# SCH_SEGEMENTOS_HORA_2.net
KiCad netlist of a schematic drawn in Altium Designer
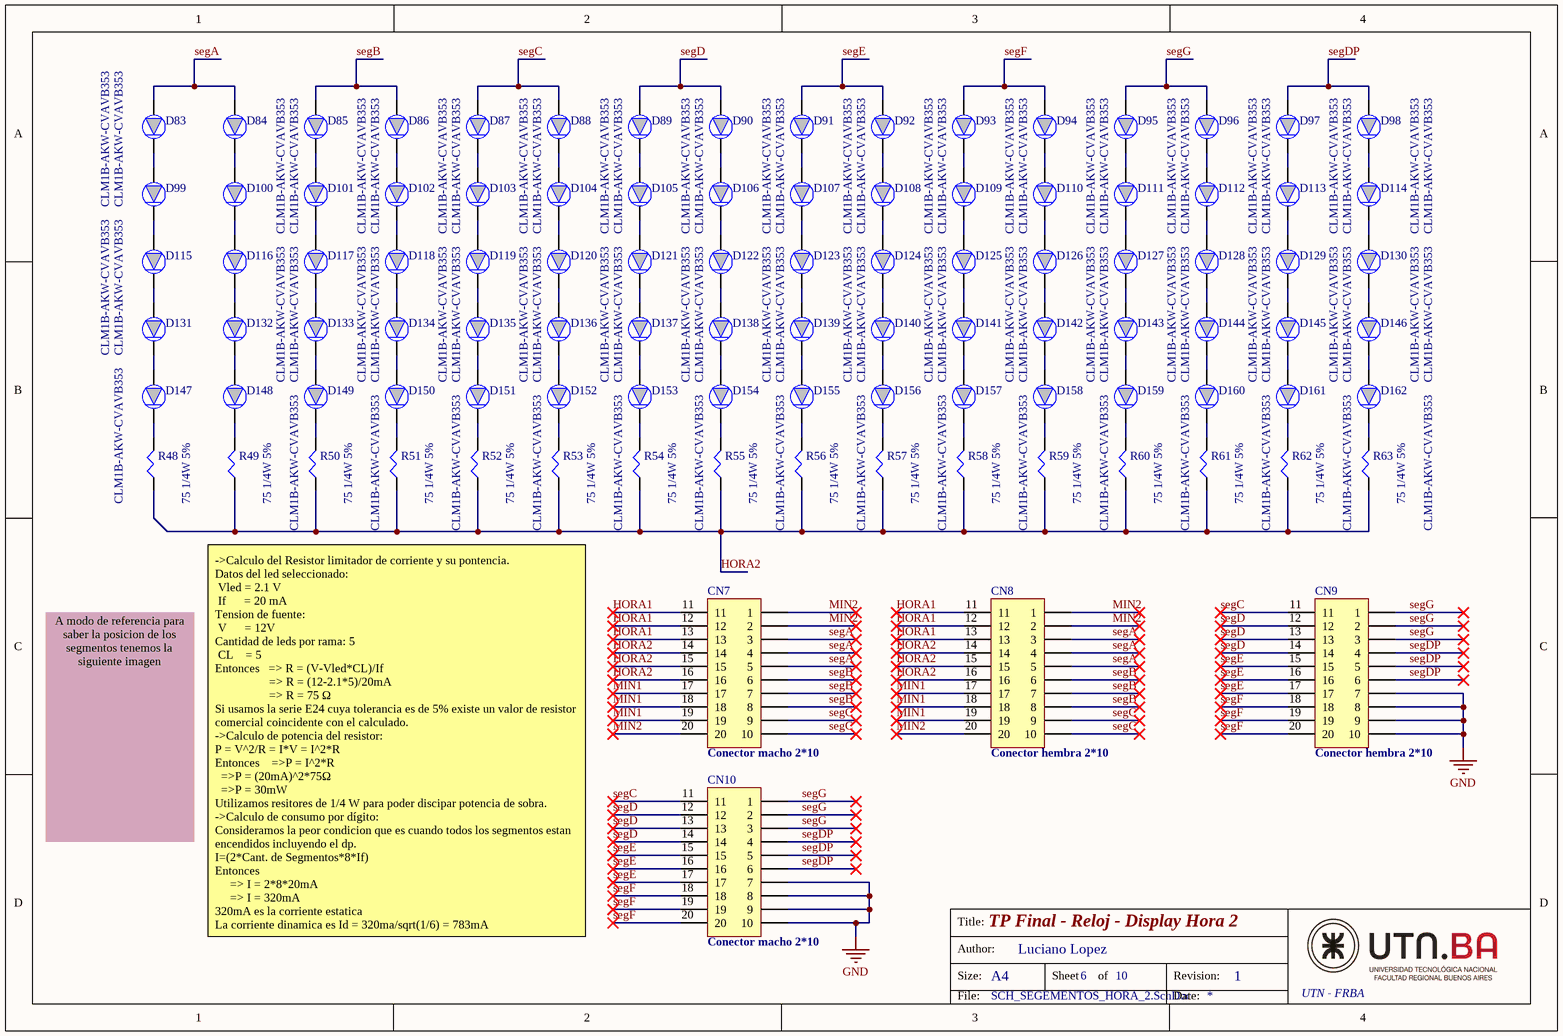
[diagram p0: SCH_SEGEMENTOS_HORA_2.SchDoc]

(export (version "E")
  (design (tool "Eeschema 10.0.6"))
  (components
    (comp (ref "CN7")
      (value "Conector macho 2*10")
      (description "Connector Generic 10 Vias")
      (libsource (lib "SCH_LIB") (part "CONN_2x10P"))
    )
    (comp (ref "CN8")
      (value "Conector hembra 2*10")
      (description "Connector Generic 10 Vias")
      (libsource (lib "SCH_LIB") (part "CONN_2x10P"))
    )
    (comp (ref "CN9")
      (value "Conector hembra 2*10")
      (description "Connector Generic 10 Vias")
      (libsource (lib "SCH_LIB") (part "CONN_2x10P"))
    )
    (comp (ref "CN10")
      (value "Conector macho 2*10")
      (description "Connector Generic 10 Vias")
      (libsource (lib "SCH_LIB") (part "CONN_2x10P"))
    )
    (comp (ref "D83")
      (value "CLM1B-AKW-CVAVB353")
      (footprint "PLCC2_LED")
      (libsource (lib "SCH_LIB") (part "LED_DIODE"))
    )
    (comp (ref "D84")
      (value "CLM1B-AKW-CVAVB353")
      (footprint "PLCC2_LED")
      (libsource (lib "SCH_LIB") (part "LED_DIODE"))
    )
    (comp (ref "D85")
      (value "CLM1B-AKW-CVAVB353")
      (footprint "PLCC2_LED")
      (libsource (lib "SCH_LIB") (part "LED_DIODE"))
    )
    (comp (ref "D86")
      (value "CLM1B-AKW-CVAVB353")
      (footprint "PLCC2_LED")
      (libsource (lib "SCH_LIB") (part "LED_DIODE"))
    )
    (comp (ref "D87")
      (value "CLM1B-AKW-CVAVB353")
      (footprint "PLCC2_LED")
      (libsource (lib "SCH_LIB") (part "LED_DIODE"))
    )
    (comp (ref "D88")
      (value "CLM1B-AKW-CVAVB353")
      (footprint "PLCC2_LED")
      (libsource (lib "SCH_LIB") (part "LED_DIODE"))
    )
    (comp (ref "D89")
      (value "CLM1B-AKW-CVAVB353")
      (footprint "PLCC2_LED")
      (libsource (lib "SCH_LIB") (part "LED_DIODE"))
    )
    (comp (ref "D90")
      (value "CLM1B-AKW-CVAVB353")
      (footprint "PLCC2_LED")
      (libsource (lib "SCH_LIB") (part "LED_DIODE"))
    )
    (comp (ref "D91")
      (value "CLM1B-AKW-CVAVB353")
      (footprint "PLCC2_LED")
      (libsource (lib "SCH_LIB") (part "LED_DIODE"))
    )
    (comp (ref "D92")
      (value "CLM1B-AKW-CVAVB353")
      (footprint "PLCC2_LED")
      (libsource (lib "SCH_LIB") (part "LED_DIODE"))
    )
    (comp (ref "D93")
      (value "CLM1B-AKW-CVAVB353")
      (footprint "PLCC2_LED")
      (libsource (lib "SCH_LIB") (part "LED_DIODE"))
    )
    (comp (ref "D94")
      (value "CLM1B-AKW-CVAVB353")
      (footprint "PLCC2_LED")
      (libsource (lib "SCH_LIB") (part "LED_DIODE"))
    )
    (comp (ref "D95")
      (value "CLM1B-AKW-CVAVB353")
      (footprint "PLCC2_LED")
      (libsource (lib "SCH_LIB") (part "LED_DIODE"))
    )
    (comp (ref "D96")
      (value "CLM1B-AKW-CVAVB353")
      (footprint "PLCC2_LED")
      (libsource (lib "SCH_LIB") (part "LED_DIODE"))
    )
    (comp (ref "D97")
      (value "CLM1B-AKW-CVAVB353")
      (footprint "PLCC2_LED")
      (libsource (lib "SCH_LIB") (part "LED_DIODE"))
    )
    (comp (ref "D98")
      (value "CLM1B-AKW-CVAVB353")
      (footprint "PLCC2_LED")
      (libsource (lib "SCH_LIB") (part "LED_DIODE"))
    )
    (comp (ref "D99")
      (value "CLM1B-AKW-CVAVB353")
      (footprint "PLCC2_LED")
      (libsource (lib "SCH_LIB") (part "LED_DIODE"))
    )
    (comp (ref "D100")
      (value "CLM1B-AKW-CVAVB353")
      (footprint "PLCC2_LED")
      (libsource (lib "SCH_LIB") (part "LED_DIODE"))
    )
    (comp (ref "D101")
      (value "CLM1B-AKW-CVAVB353")
      (footprint "PLCC2_LED")
      (libsource (lib "SCH_LIB") (part "LED_DIODE"))
    )
    (comp (ref "D102")
      (value "CLM1B-AKW-CVAVB353")
      (footprint "PLCC2_LED")
      (libsource (lib "SCH_LIB") (part "LED_DIODE"))
    )
    (comp (ref "D103")
      (value "CLM1B-AKW-CVAVB353")
      (footprint "PLCC2_LED")
      (libsource (lib "SCH_LIB") (part "LED_DIODE"))
    )
    (comp (ref "D104")
      (value "CLM1B-AKW-CVAVB353")
      (footprint "PLCC2_LED")
      (libsource (lib "SCH_LIB") (part "LED_DIODE"))
    )
    (comp (ref "D105")
      (value "CLM1B-AKW-CVAVB353")
      (footprint "PLCC2_LED")
      (libsource (lib "SCH_LIB") (part "LED_DIODE"))
    )
    (comp (ref "D106")
      (value "CLM1B-AKW-CVAVB353")
      (footprint "PLCC2_LED")
      (libsource (lib "SCH_LIB") (part "LED_DIODE"))
    )
    (comp (ref "D107")
      (value "CLM1B-AKW-CVAVB353")
      (footprint "PLCC2_LED")
      (libsource (lib "SCH_LIB") (part "LED_DIODE"))
    )
    (comp (ref "D108")
      (value "CLM1B-AKW-CVAVB353")
      (footprint "PLCC2_LED")
      (libsource (lib "SCH_LIB") (part "LED_DIODE"))
    )
    (comp (ref "D109")
      (value "CLM1B-AKW-CVAVB353")
      (footprint "PLCC2_LED")
      (libsource (lib "SCH_LIB") (part "LED_DIODE"))
    )
    (comp (ref "D110")
      (value "CLM1B-AKW-CVAVB353")
      (footprint "PLCC2_LED")
      (libsource (lib "SCH_LIB") (part "LED_DIODE"))
    )
    (comp (ref "D111")
      (value "CLM1B-AKW-CVAVB353")
      (footprint "PLCC2_LED")
      (libsource (lib "SCH_LIB") (part "LED_DIODE"))
    )
    (comp (ref "D112")
      (value "CLM1B-AKW-CVAVB353")
      (footprint "PLCC2_LED")
      (libsource (lib "SCH_LIB") (part "LED_DIODE"))
    )
    (comp (ref "D113")
      (value "CLM1B-AKW-CVAVB353")
      (footprint "PLCC2_LED")
      (libsource (lib "SCH_LIB") (part "LED_DIODE"))
    )
    (comp (ref "D114")
      (value "CLM1B-AKW-CVAVB353")
      (footprint "PLCC2_LED")
      (libsource (lib "SCH_LIB") (part "LED_DIODE"))
    )
    (comp (ref "D115")
      (value "CLM1B-AKW-CVAVB353")
      (footprint "PLCC2_LED")
      (libsource (lib "SCH_LIB") (part "LED_DIODE"))
    )
    (comp (ref "D116")
      (value "CLM1B-AKW-CVAVB353")
      (footprint "PLCC2_LED")
      (libsource (lib "SCH_LIB") (part "LED_DIODE"))
    )
    (comp (ref "D117")
      (value "CLM1B-AKW-CVAVB353")
      (footprint "PLCC2_LED")
      (libsource (lib "SCH_LIB") (part "LED_DIODE"))
    )
    (comp (ref "D118")
      (value "CLM1B-AKW-CVAVB353")
      (footprint "PLCC2_LED")
      (libsource (lib "SCH_LIB") (part "LED_DIODE"))
    )
    (comp (ref "D119")
      (value "CLM1B-AKW-CVAVB353")
      (footprint "PLCC2_LED")
      (libsource (lib "SCH_LIB") (part "LED_DIODE"))
    )
    (comp (ref "D120")
      (value "CLM1B-AKW-CVAVB353")
      (footprint "PLCC2_LED")
      (libsource (lib "SCH_LIB") (part "LED_DIODE"))
    )
    (comp (ref "D121")
      (value "CLM1B-AKW-CVAVB353")
      (footprint "PLCC2_LED")
      (libsource (lib "SCH_LIB") (part "LED_DIODE"))
    )
    (comp (ref "D122")
      (value "CLM1B-AKW-CVAVB353")
      (footprint "PLCC2_LED")
      (libsource (lib "SCH_LIB") (part "LED_DIODE"))
    )
    (comp (ref "D123")
      (value "CLM1B-AKW-CVAVB353")
      (footprint "PLCC2_LED")
      (libsource (lib "SCH_LIB") (part "LED_DIODE"))
    )
    (comp (ref "D124")
      (value "CLM1B-AKW-CVAVB353")
      (footprint "PLCC2_LED")
      (libsource (lib "SCH_LIB") (part "LED_DIODE"))
    )
    (comp (ref "D125")
      (value "CLM1B-AKW-CVAVB353")
      (footprint "PLCC2_LED")
      (libsource (lib "SCH_LIB") (part "LED_DIODE"))
    )
    (comp (ref "D126")
      (value "CLM1B-AKW-CVAVB353")
      (footprint "PLCC2_LED")
      (libsource (lib "SCH_LIB") (part "LED_DIODE"))
    )
    (comp (ref "D127")
      (value "CLM1B-AKW-CVAVB353")
      (footprint "PLCC2_LED")
      (libsource (lib "SCH_LIB") (part "LED_DIODE"))
    )
    (comp (ref "D128")
      (value "CLM1B-AKW-CVAVB353")
      (footprint "PLCC2_LED")
      (libsource (lib "SCH_LIB") (part "LED_DIODE"))
    )
    (comp (ref "D129")
      (value "CLM1B-AKW-CVAVB353")
      (footprint "PLCC2_LED")
      (libsource (lib "SCH_LIB") (part "LED_DIODE"))
    )
    (comp (ref "D130")
      (value "CLM1B-AKW-CVAVB353")
      (footprint "PLCC2_LED")
      (libsource (lib "SCH_LIB") (part "LED_DIODE"))
    )
    (comp (ref "D131")
      (value "CLM1B-AKW-CVAVB353")
      (footprint "PLCC2_LED")
      (libsource (lib "SCH_LIB") (part "LED_DIODE"))
    )
    (comp (ref "D132")
      (value "CLM1B-AKW-CVAVB353")
      (footprint "PLCC2_LED")
      (libsource (lib "SCH_LIB") (part "LED_DIODE"))
    )
    (comp (ref "D133")
      (value "CLM1B-AKW-CVAVB353")
      (footprint "PLCC2_LED")
      (libsource (lib "SCH_LIB") (part "LED_DIODE"))
    )
    (comp (ref "D134")
      (value "CLM1B-AKW-CVAVB353")
      (footprint "PLCC2_LED")
      (libsource (lib "SCH_LIB") (part "LED_DIODE"))
    )
    (comp (ref "D135")
      (value "CLM1B-AKW-CVAVB353")
      (footprint "PLCC2_LED")
      (libsource (lib "SCH_LIB") (part "LED_DIODE"))
    )
    (comp (ref "D136")
      (value "CLM1B-AKW-CVAVB353")
      (footprint "PLCC2_LED")
      (libsource (lib "SCH_LIB") (part "LED_DIODE"))
    )
    (comp (ref "D137")
      (value "CLM1B-AKW-CVAVB353")
      (footprint "PLCC2_LED")
      (libsource (lib "SCH_LIB") (part "LED_DIODE"))
    )
    (comp (ref "D138")
      (value "CLM1B-AKW-CVAVB353")
      (footprint "PLCC2_LED")
      (libsource (lib "SCH_LIB") (part "LED_DIODE"))
    )
    (comp (ref "D139")
      (value "CLM1B-AKW-CVAVB353")
      (footprint "PLCC2_LED")
      (libsource (lib "SCH_LIB") (part "LED_DIODE"))
    )
    (comp (ref "D140")
      (value "CLM1B-AKW-CVAVB353")
      (footprint "PLCC2_LED")
      (libsource (lib "SCH_LIB") (part "LED_DIODE"))
    )
    (comp (ref "D141")
      (value "CLM1B-AKW-CVAVB353")
      (footprint "PLCC2_LED")
      (libsource (lib "SCH_LIB") (part "LED_DIODE"))
    )
    (comp (ref "D142")
      (value "CLM1B-AKW-CVAVB353")
      (footprint "PLCC2_LED")
      (libsource (lib "SCH_LIB") (part "LED_DIODE"))
    )
    (comp (ref "D143")
      (value "CLM1B-AKW-CVAVB353")
      (footprint "PLCC2_LED")
      (libsource (lib "SCH_LIB") (part "LED_DIODE"))
    )
    (comp (ref "D144")
      (value "CLM1B-AKW-CVAVB353")
      (footprint "PLCC2_LED")
      (libsource (lib "SCH_LIB") (part "LED_DIODE"))
    )
    (comp (ref "D145")
      (value "CLM1B-AKW-CVAVB353")
      (footprint "PLCC2_LED")
      (libsource (lib "SCH_LIB") (part "LED_DIODE"))
    )
    (comp (ref "D146")
      (value "CLM1B-AKW-CVAVB353")
      (footprint "PLCC2_LED")
      (libsource (lib "SCH_LIB") (part "LED_DIODE"))
    )
    (comp (ref "D147")
      (value "CLM1B-AKW-CVAVB353")
      (footprint "PLCC2_LED")
      (libsource (lib "SCH_LIB") (part "LED_DIODE"))
    )
    (comp (ref "D148")
      (value "CLM1B-AKW-CVAVB353")
      (footprint "PLCC2_LED")
      (libsource (lib "SCH_LIB") (part "LED_DIODE"))
    )
    (comp (ref "D149")
      (value "CLM1B-AKW-CVAVB353")
      (footprint "PLCC2_LED")
      (libsource (lib "SCH_LIB") (part "LED_DIODE"))
    )
    (comp (ref "D150")
      (value "CLM1B-AKW-CVAVB353")
      (footprint "PLCC2_LED")
      (libsource (lib "SCH_LIB") (part "LED_DIODE"))
    )
    (comp (ref "D151")
      (value "CLM1B-AKW-CVAVB353")
      (footprint "PLCC2_LED")
      (libsource (lib "SCH_LIB") (part "LED_DIODE"))
    )
    (comp (ref "D152")
      (value "CLM1B-AKW-CVAVB353")
      (footprint "PLCC2_LED")
      (libsource (lib "SCH_LIB") (part "LED_DIODE"))
    )
    (comp (ref "D153")
      (value "CLM1B-AKW-CVAVB353")
      (footprint "PLCC2_LED")
      (libsource (lib "SCH_LIB") (part "LED_DIODE"))
    )
    (comp (ref "D154")
      (value "CLM1B-AKW-CVAVB353")
      (footprint "PLCC2_LED")
      (libsource (lib "SCH_LIB") (part "LED_DIODE"))
    )
    (comp (ref "D155")
      (value "CLM1B-AKW-CVAVB353")
      (footprint "PLCC2_LED")
      (libsource (lib "SCH_LIB") (part "LED_DIODE"))
    )
    (comp (ref "D156")
      (value "CLM1B-AKW-CVAVB353")
      (footprint "PLCC2_LED")
      (libsource (lib "SCH_LIB") (part "LED_DIODE"))
    )
    (comp (ref "D157")
      (value "CLM1B-AKW-CVAVB353")
      (footprint "PLCC2_LED")
      (libsource (lib "SCH_LIB") (part "LED_DIODE"))
    )
    (comp (ref "D158")
      (value "CLM1B-AKW-CVAVB353")
      (footprint "PLCC2_LED")
      (libsource (lib "SCH_LIB") (part "LED_DIODE"))
    )
    (comp (ref "D159")
      (value "CLM1B-AKW-CVAVB353")
      (footprint "PLCC2_LED")
      (libsource (lib "SCH_LIB") (part "LED_DIODE"))
    )
    (comp (ref "D160")
      (value "CLM1B-AKW-CVAVB353")
      (footprint "PLCC2_LED")
      (libsource (lib "SCH_LIB") (part "LED_DIODE"))
    )
    (comp (ref "D161")
      (value "CLM1B-AKW-CVAVB353")
      (footprint "PLCC2_LED")
      (libsource (lib "SCH_LIB") (part "LED_DIODE"))
    )
    (comp (ref "D162")
      (value "CLM1B-AKW-CVAVB353")
      (footprint "PLCC2_LED")
      (libsource (lib "SCH_LIB") (part "LED_DIODE"))
    )
    (comp (ref "R48") (value "75 1/4W 5%") (footprint "R_0805") (libsource (lib "SCH_LIB") (part "Resistor")))
    (comp (ref "R49") (value "75 1/4W 5%") (footprint "R_0805") (libsource (lib "SCH_LIB") (part "Resistor")))
    (comp (ref "R50") (value "75 1/4W 5%") (footprint "R_0805") (libsource (lib "SCH_LIB") (part "Resistor")))
    (comp (ref "R51") (value "75 1/4W 5%") (footprint "R_0805") (libsource (lib "SCH_LIB") (part "Resistor")))
    (comp (ref "R52") (value "75 1/4W 5%") (footprint "R_0805") (libsource (lib "SCH_LIB") (part "Resistor")))
    (comp (ref "R53") (value "75 1/4W 5%") (footprint "R_0805") (libsource (lib "SCH_LIB") (part "Resistor")))
    (comp (ref "R54") (value "75 1/4W 5%") (footprint "R_0805") (libsource (lib "SCH_LIB") (part "Resistor")))
    (comp (ref "R55") (value "75 1/4W 5%") (footprint "R_0805") (libsource (lib "SCH_LIB") (part "Resistor")))
    (comp (ref "R56") (value "75 1/4W 5%") (footprint "R_0805") (libsource (lib "SCH_LIB") (part "Resistor")))
    (comp (ref "R57") (value "75 1/4W 5%") (footprint "R_0805") (libsource (lib "SCH_LIB") (part "Resistor")))
    (comp (ref "R58") (value "75 1/4W 5%") (footprint "R_0805") (libsource (lib "SCH_LIB") (part "Resistor")))
    (comp (ref "R59") (value "75 1/4W 5%") (footprint "R_0805") (libsource (lib "SCH_LIB") (part "Resistor")))
    (comp (ref "R60") (value "75 1/4W 5%") (footprint "R_0805") (libsource (lib "SCH_LIB") (part "Resistor")))
    (comp (ref "R61") (value "75 1/4W 5%") (footprint "R_0805") (libsource (lib "SCH_LIB") (part "Resistor")))
    (comp (ref "R62") (value "75 1/4W 5%") (footprint "R_0805") (libsource (lib "SCH_LIB") (part "Resistor")))
    (comp (ref "R63") (value "75 1/4W 5%") (footprint "R_0805") (libsource (lib "SCH_LIB") (part "Resistor")))
  )
  (nets
    (net (code "1") (name "/HORA1") (class "Default")
      (node (ref "CN7") (pin "11") (pinfunction "11_11") (pintype "passive"))
      (node (ref "CN7") (pin "12") (pinfunction "12_12") (pintype "passive"))
      (node (ref "CN7") (pin "13") (pinfunction "13_13") (pintype "passive"))
      (node (ref "CN8") (pin "11") (pinfunction "11_11") (pintype "passive"))
      (node (ref "CN8") (pin "12") (pinfunction "12_12") (pintype "passive"))
      (node (ref "CN8") (pin "13") (pinfunction "13_13") (pintype "passive"))
    )
    (net (code "2") (name "/HORA2") (class "Default")
      (node (ref "CN7") (pin "14") (pinfunction "14_14") (pintype "passive"))
      (node (ref "CN7") (pin "15") (pinfunction "15_15") (pintype "passive"))
      (node (ref "CN7") (pin "16") (pinfunction "16_16") (pintype "passive"))
      (node (ref "CN8") (pin "14") (pinfunction "14_14") (pintype "passive"))
      (node (ref "CN8") (pin "15") (pinfunction "15_15") (pintype "passive"))
      (node (ref "CN8") (pin "16") (pinfunction "16_16") (pintype "passive"))
      (node (ref "R48") (pin "47") (pinfunction "47_47") (pintype "passive"))
      (node (ref "R49") (pin "47") (pinfunction "47_47") (pintype "passive"))
      (node (ref "R50") (pin "47") (pinfunction "47_47") (pintype "passive"))
      (node (ref "R51") (pin "47") (pinfunction "47_47") (pintype "passive"))
      (node (ref "R52") (pin "47") (pinfunction "47_47") (pintype "passive"))
      (node (ref "R53") (pin "47") (pinfunction "47_47") (pintype "passive"))
      (node (ref "R54") (pin "47") (pinfunction "47_47") (pintype "passive"))
      (node (ref "R55") (pin "47") (pinfunction "47_47") (pintype "passive"))
      (node (ref "R56") (pin "47") (pinfunction "47_47") (pintype "passive"))
      (node (ref "R57") (pin "47") (pinfunction "47_47") (pintype "passive"))
      (node (ref "R58") (pin "47") (pinfunction "47_47") (pintype "passive"))
      (node (ref "R59") (pin "47") (pinfunction "47_47") (pintype "passive"))
      (node (ref "R60") (pin "47") (pinfunction "47_47") (pintype "passive"))
      (node (ref "R61") (pin "47") (pinfunction "47_47") (pintype "passive"))
      (node (ref "R62") (pin "47") (pinfunction "47_47") (pintype "passive"))
      (node (ref "R63") (pin "47") (pinfunction "47_47") (pintype "passive"))
    )
    (net (code "3") (name "/MIN1") (class "Default")
      (node (ref "CN7") (pin "17") (pinfunction "17_17") (pintype "passive"))
      (node (ref "CN7") (pin "18") (pinfunction "18_18") (pintype "passive"))
      (node (ref "CN7") (pin "19") (pinfunction "19_19") (pintype "passive"))
      (node (ref "CN8") (pin "17") (pinfunction "17_17") (pintype "passive"))
      (node (ref "CN8") (pin "18") (pinfunction "18_18") (pintype "passive"))
      (node (ref "CN8") (pin "19") (pinfunction "19_19") (pintype "passive"))
    )
    (net (code "4") (name "/MIN2") (class "Default")
      (node (ref "CN7") (pin "1") (pinfunction "1_1") (pintype "passive"))
      (node (ref "CN7") (pin "2") (pinfunction "2_2") (pintype "passive"))
      (node (ref "CN7") (pin "20") (pinfunction "20_20") (pintype "passive"))
      (node (ref "CN8") (pin "1") (pinfunction "1_1") (pintype "passive"))
      (node (ref "CN8") (pin "2") (pinfunction "2_2") (pintype "passive"))
      (node (ref "CN8") (pin "20") (pinfunction "20_20") (pintype "passive"))
    )
    (net (code "5") (name "/segA") (class "Default")
      (node (ref "CN7") (pin "3") (pinfunction "3_3") (pintype "passive"))
      (node (ref "CN7") (pin "4") (pinfunction "4_4") (pintype "passive"))
      (node (ref "CN7") (pin "5") (pinfunction "5_5") (pintype "passive"))
      (node (ref "CN8") (pin "3") (pinfunction "3_3") (pintype "passive"))
      (node (ref "CN8") (pin "4") (pinfunction "4_4") (pintype "passive"))
      (node (ref "CN8") (pin "5") (pinfunction "5_5") (pintype "passive"))
      (node (ref "D83") (pin "12") (pinfunction "12_12") (pintype "passive"))
      (node (ref "D84") (pin "12") (pinfunction "12_12") (pintype "passive"))
    )
    (net (code "6") (name "/segB") (class "Default")
      (node (ref "CN7") (pin "6") (pinfunction "6_6") (pintype "passive"))
      (node (ref "CN7") (pin "7") (pinfunction "7_7") (pintype "passive"))
      (node (ref "CN7") (pin "8") (pinfunction "8_8") (pintype "passive"))
      (node (ref "CN8") (pin "6") (pinfunction "6_6") (pintype "passive"))
      (node (ref "CN8") (pin "7") (pinfunction "7_7") (pintype "passive"))
      (node (ref "CN8") (pin "8") (pinfunction "8_8") (pintype "passive"))
      (node (ref "D85") (pin "12") (pinfunction "12_12") (pintype "passive"))
      (node (ref "D86") (pin "12") (pinfunction "12_12") (pintype "passive"))
    )
    (net (code "7") (name "/segC") (class "Default")
      (node (ref "CN10") (pin "11") (pinfunction "11_11") (pintype "passive"))
      (node (ref "CN7") (pin "10") (pinfunction "10_10") (pintype "passive"))
      (node (ref "CN7") (pin "9") (pinfunction "9_9") (pintype "passive"))
      (node (ref "CN8") (pin "10") (pinfunction "10_10") (pintype "passive"))
      (node (ref "CN8") (pin "9") (pinfunction "9_9") (pintype "passive"))
      (node (ref "CN9") (pin "11") (pinfunction "11_11") (pintype "passive"))
      (node (ref "D87") (pin "12") (pinfunction "12_12") (pintype "passive"))
      (node (ref "D88") (pin "12") (pinfunction "12_12") (pintype "passive"))
    )
    (net (code "8") (name "/segD") (class "Default")
      (node (ref "CN10") (pin "12") (pinfunction "12_12") (pintype "passive"))
      (node (ref "CN10") (pin "13") (pinfunction "13_13") (pintype "passive"))
      (node (ref "CN10") (pin "14") (pinfunction "14_14") (pintype "passive"))
      (node (ref "CN9") (pin "12") (pinfunction "12_12") (pintype "passive"))
      (node (ref "CN9") (pin "13") (pinfunction "13_13") (pintype "passive"))
      (node (ref "CN9") (pin "14") (pinfunction "14_14") (pintype "passive"))
      (node (ref "D89") (pin "12") (pinfunction "12_12") (pintype "passive"))
      (node (ref "D90") (pin "12") (pinfunction "12_12") (pintype "passive"))
    )
    (net (code "9") (name "/segDP") (class "Default")
      (node (ref "CN10") (pin "4") (pinfunction "4_4") (pintype "passive"))
      (node (ref "CN10") (pin "5") (pinfunction "5_5") (pintype "passive"))
      (node (ref "CN10") (pin "6") (pinfunction "6_6") (pintype "passive"))
      (node (ref "CN9") (pin "4") (pinfunction "4_4") (pintype "passive"))
      (node (ref "CN9") (pin "5") (pinfunction "5_5") (pintype "passive"))
      (node (ref "CN9") (pin "6") (pinfunction "6_6") (pintype "passive"))
      (node (ref "D97") (pin "12") (pinfunction "12_12") (pintype "passive"))
      (node (ref "D98") (pin "12") (pinfunction "12_12") (pintype "passive"))
    )
    (net (code "10") (name "/segE") (class "Default")
      (node (ref "CN10") (pin "15") (pinfunction "15_15") (pintype "passive"))
      (node (ref "CN10") (pin "16") (pinfunction "16_16") (pintype "passive"))
      (node (ref "CN10") (pin "17") (pinfunction "17_17") (pintype "passive"))
      (node (ref "CN9") (pin "15") (pinfunction "15_15") (pintype "passive"))
      (node (ref "CN9") (pin "16") (pinfunction "16_16") (pintype "passive"))
      (node (ref "CN9") (pin "17") (pinfunction "17_17") (pintype "passive"))
      (node (ref "D91") (pin "12") (pinfunction "12_12") (pintype "passive"))
      (node (ref "D92") (pin "12") (pinfunction "12_12") (pintype "passive"))
    )
    (net (code "11") (name "/segF") (class "Default")
      (node (ref "CN10") (pin "18") (pinfunction "18_18") (pintype "passive"))
      (node (ref "CN10") (pin "19") (pinfunction "19_19") (pintype "passive"))
      (node (ref "CN10") (pin "20") (pinfunction "20_20") (pintype "passive"))
      (node (ref "CN9") (pin "18") (pinfunction "18_18") (pintype "passive"))
      (node (ref "CN9") (pin "19") (pinfunction "19_19") (pintype "passive"))
      (node (ref "CN9") (pin "20") (pinfunction "20_20") (pintype "passive"))
      (node (ref "D93") (pin "12") (pinfunction "12_12") (pintype "passive"))
      (node (ref "D94") (pin "12") (pinfunction "12_12") (pintype "passive"))
    )
    (net (code "12") (name "/segG") (class "Default")
      (node (ref "CN10") (pin "1") (pinfunction "1_1") (pintype "passive"))
      (node (ref "CN10") (pin "2") (pinfunction "2_2") (pintype "passive"))
      (node (ref "CN10") (pin "3") (pinfunction "3_3") (pintype "passive"))
      (node (ref "CN9") (pin "1") (pinfunction "1_1") (pintype "passive"))
      (node (ref "CN9") (pin "2") (pinfunction "2_2") (pintype "passive"))
      (node (ref "CN9") (pin "3") (pinfunction "3_3") (pintype "passive"))
      (node (ref "D95") (pin "12") (pinfunction "12_12") (pintype "passive"))
      (node (ref "D96") (pin "12") (pinfunction "12_12") (pintype "passive"))
    )
    (net (code "13") (name "GND") (class "Default")
      (node (ref "CN10") (pin "10") (pinfunction "10_10") (pintype "passive"))
      (node (ref "CN10") (pin "7") (pinfunction "7_7") (pintype "passive"))
      (node (ref "CN10") (pin "8") (pinfunction "8_8") (pintype "passive"))
      (node (ref "CN10") (pin "9") (pinfunction "9_9") (pintype "passive"))
      (node (ref "CN9") (pin "10") (pinfunction "10_10") (pintype "passive"))
      (node (ref "CN9") (pin "7") (pinfunction "7_7") (pintype "passive"))
      (node (ref "CN9") (pin "8") (pinfunction "8_8") (pintype "passive"))
      (node (ref "CN9") (pin "9") (pinfunction "9_9") (pintype "passive"))
    )
    (net (code "14") (name "Net-(D83-Pad11)") (class "Default")
      (node (ref "D83") (pin "11") (pinfunction "11_11") (pintype "passive"))
      (node (ref "D99") (pin "12") (pinfunction "12_12") (pintype "passive"))
    )
    (net (code "15") (name "Net-(D100-Pad11)") (class "Default")
      (node (ref "D100") (pin "11") (pinfunction "11_11") (pintype "passive"))
      (node (ref "D116") (pin "12") (pinfunction "12_12") (pintype "passive"))
    )
    (net (code "16") (name "Net-(D100-Pad12)") (class "Default")
      (node (ref "D100") (pin "12") (pinfunction "12_12") (pintype "passive"))
      (node (ref "D84") (pin "11") (pinfunction "11_11") (pintype "passive"))
    )
    (net (code "17") (name "Net-(D101-Pad11)") (class "Default")
      (node (ref "D101") (pin "11") (pinfunction "11_11") (pintype "passive"))
      (node (ref "D117") (pin "12") (pinfunction "12_12") (pintype "passive"))
    )
    (net (code "18") (name "Net-(D101-Pad12)") (class "Default")
      (node (ref "D101") (pin "12") (pinfunction "12_12") (pintype "passive"))
      (node (ref "D85") (pin "11") (pinfunction "11_11") (pintype "passive"))
    )
    (net (code "19") (name "Net-(D102-Pad11)") (class "Default")
      (node (ref "D102") (pin "11") (pinfunction "11_11") (pintype "passive"))
      (node (ref "D118") (pin "12") (pinfunction "12_12") (pintype "passive"))
    )
    (net (code "20") (name "Net-(D102-Pad12)") (class "Default")
      (node (ref "D102") (pin "12") (pinfunction "12_12") (pintype "passive"))
      (node (ref "D86") (pin "11") (pinfunction "11_11") (pintype "passive"))
    )
    (net (code "21") (name "Net-(D103-Pad11)") (class "Default")
      (node (ref "D103") (pin "11") (pinfunction "11_11") (pintype "passive"))
      (node (ref "D119") (pin "12") (pinfunction "12_12") (pintype "passive"))
    )
    (net (code "22") (name "Net-(D103-Pad12)") (class "Default")
      (node (ref "D103") (pin "12") (pinfunction "12_12") (pintype "passive"))
      (node (ref "D87") (pin "11") (pinfunction "11_11") (pintype "passive"))
    )
    (net (code "23") (name "Net-(D104-Pad11)") (class "Default")
      (node (ref "D104") (pin "11") (pinfunction "11_11") (pintype "passive"))
      (node (ref "D120") (pin "12") (pinfunction "12_12") (pintype "passive"))
    )
    (net (code "24") (name "Net-(D104-Pad12)") (class "Default")
      (node (ref "D104") (pin "12") (pinfunction "12_12") (pintype "passive"))
      (node (ref "D88") (pin "11") (pinfunction "11_11") (pintype "passive"))
    )
    (net (code "25") (name "Net-(D105-Pad11)") (class "Default")
      (node (ref "D105") (pin "11") (pinfunction "11_11") (pintype "passive"))
      (node (ref "D121") (pin "12") (pinfunction "12_12") (pintype "passive"))
    )
    (net (code "26") (name "Net-(D105-Pad12)") (class "Default")
      (node (ref "D105") (pin "12") (pinfunction "12_12") (pintype "passive"))
      (node (ref "D89") (pin "11") (pinfunction "11_11") (pintype "passive"))
    )
    (net (code "27") (name "Net-(D106-Pad11)") (class "Default")
      (node (ref "D106") (pin "11") (pinfunction "11_11") (pintype "passive"))
      (node (ref "D122") (pin "12") (pinfunction "12_12") (pintype "passive"))
    )
    (net (code "28") (name "Net-(D106-Pad12)") (class "Default")
      (node (ref "D106") (pin "12") (pinfunction "12_12") (pintype "passive"))
      (node (ref "D90") (pin "11") (pinfunction "11_11") (pintype "passive"))
    )
    (net (code "29") (name "Net-(D107-Pad11)") (class "Default")
      (node (ref "D107") (pin "11") (pinfunction "11_11") (pintype "passive"))
      (node (ref "D123") (pin "12") (pinfunction "12_12") (pintype "passive"))
    )
    (net (code "30") (name "Net-(D107-Pad12)") (class "Default")
      (node (ref "D107") (pin "12") (pinfunction "12_12") (pintype "passive"))
      (node (ref "D91") (pin "11") (pinfunction "11_11") (pintype "passive"))
    )
    (net (code "31") (name "Net-(D108-Pad11)") (class "Default")
      (node (ref "D108") (pin "11") (pinfunction "11_11") (pintype "passive"))
      (node (ref "D124") (pin "12") (pinfunction "12_12") (pintype "passive"))
    )
    (net (code "32") (name "Net-(D108-Pad12)") (class "Default")
      (node (ref "D108") (pin "12") (pinfunction "12_12") (pintype "passive"))
      (node (ref "D92") (pin "11") (pinfunction "11_11") (pintype "passive"))
    )
    (net (code "33") (name "Net-(D109-Pad11)") (class "Default")
      (node (ref "D109") (pin "11") (pinfunction "11_11") (pintype "passive"))
      (node (ref "D125") (pin "12") (pinfunction "12_12") (pintype "passive"))
    )
    (net (code "34") (name "Net-(D109-Pad12)") (class "Default")
      (node (ref "D109") (pin "12") (pinfunction "12_12") (pintype "passive"))
      (node (ref "D93") (pin "11") (pinfunction "11_11") (pintype "passive"))
    )
    (net (code "35") (name "Net-(D110-Pad11)") (class "Default")
      (node (ref "D110") (pin "11") (pinfunction "11_11") (pintype "passive"))
      (node (ref "D126") (pin "12") (pinfunction "12_12") (pintype "passive"))
    )
    (net (code "36") (name "Net-(D110-Pad12)") (class "Default")
      (node (ref "D110") (pin "12") (pinfunction "12_12") (pintype "passive"))
      (node (ref "D94") (pin "11") (pinfunction "11_11") (pintype "passive"))
    )
    (net (code "37") (name "Net-(D111-Pad11)") (class "Default")
      (node (ref "D111") (pin "11") (pinfunction "11_11") (pintype "passive"))
      (node (ref "D127") (pin "12") (pinfunction "12_12") (pintype "passive"))
    )
    (net (code "38") (name "Net-(D111-Pad12)") (class "Default")
      (node (ref "D111") (pin "12") (pinfunction "12_12") (pintype "passive"))
      (node (ref "D95") (pin "11") (pinfunction "11_11") (pintype "passive"))
    )
    (net (code "39") (name "Net-(D112-Pad11)") (class "Default")
      (node (ref "D112") (pin "11") (pinfunction "11_11") (pintype "passive"))
      (node (ref "D128") (pin "12") (pinfunction "12_12") (pintype "passive"))
    )
    (net (code "40") (name "Net-(D112-Pad12)") (class "Default")
      (node (ref "D112") (pin "12") (pinfunction "12_12") (pintype "passive"))
      (node (ref "D96") (pin "11") (pinfunction "11_11") (pintype "passive"))
    )
    (net (code "41") (name "Net-(D113-Pad11)") (class "Default")
      (node (ref "D113") (pin "11") (pinfunction "11_11") (pintype "passive"))
      (node (ref "D129") (pin "12") (pinfunction "12_12") (pintype "passive"))
    )
    (net (code "42") (name "Net-(D113-Pad12)") (class "Default")
      (node (ref "D113") (pin "12") (pinfunction "12_12") (pintype "passive"))
      (node (ref "D97") (pin "11") (pinfunction "11_11") (pintype "passive"))
    )
    (net (code "43") (name "Net-(D114-Pad11)") (class "Default")
      (node (ref "D114") (pin "11") (pinfunction "11_11") (pintype "passive"))
      (node (ref "D130") (pin "12") (pinfunction "12_12") (pintype "passive"))
    )
    (net (code "44") (name "Net-(D114-Pad12)") (class "Default")
      (node (ref "D114") (pin "12") (pinfunction "12_12") (pintype "passive"))
      (node (ref "D98") (pin "11") (pinfunction "11_11") (pintype "passive"))
    )
    (net (code "45") (name "Net-(D115-Pad11)") (class "Default")
      (node (ref "D115") (pin "11") (pinfunction "11_11") (pintype "passive"))
      (node (ref "D131") (pin "12") (pinfunction "12_12") (pintype "passive"))
    )
    (net (code "46") (name "Net-(D115-Pad12)") (class "Default")
      (node (ref "D115") (pin "12") (pinfunction "12_12") (pintype "passive"))
      (node (ref "D99") (pin "11") (pinfunction "11_11") (pintype "passive"))
    )
    (net (code "47") (name "Net-(D116-Pad11)") (class "Default")
      (node (ref "D116") (pin "11") (pinfunction "11_11") (pintype "passive"))
      (node (ref "D132") (pin "12") (pinfunction "12_12") (pintype "passive"))
    )
    (net (code "48") (name "Net-(D117-Pad11)") (class "Default")
      (node (ref "D117") (pin "11") (pinfunction "11_11") (pintype "passive"))
      (node (ref "D133") (pin "12") (pinfunction "12_12") (pintype "passive"))
    )
    (net (code "49") (name "Net-(D118-Pad11)") (class "Default")
      (node (ref "D118") (pin "11") (pinfunction "11_11") (pintype "passive"))
      (node (ref "D134") (pin "12") (pinfunction "12_12") (pintype "passive"))
    )
    (net (code "50") (name "Net-(D119-Pad11)") (class "Default")
      (node (ref "D119") (pin "11") (pinfunction "11_11") (pintype "passive"))
      (node (ref "D135") (pin "12") (pinfunction "12_12") (pintype "passive"))
    )
    (net (code "51") (name "Net-(D120-Pad11)") (class "Default")
      (node (ref "D120") (pin "11") (pinfunction "11_11") (pintype "passive"))
      (node (ref "D136") (pin "12") (pinfunction "12_12") (pintype "passive"))
    )
    (net (code "52") (name "Net-(D121-Pad11)") (class "Default")
      (node (ref "D121") (pin "11") (pinfunction "11_11") (pintype "passive"))
      (node (ref "D137") (pin "12") (pinfunction "12_12") (pintype "passive"))
    )
    (net (code "53") (name "Net-(D122-Pad11)") (class "Default")
      (node (ref "D122") (pin "11") (pinfunction "11_11") (pintype "passive"))
      (node (ref "D138") (pin "12") (pinfunction "12_12") (pintype "passive"))
    )
    (net (code "54") (name "Net-(D123-Pad11)") (class "Default")
      (node (ref "D123") (pin "11") (pinfunction "11_11") (pintype "passive"))
      (node (ref "D139") (pin "12") (pinfunction "12_12") (pintype "passive"))
    )
    (net (code "55") (name "Net-(D124-Pad11)") (class "Default")
      (node (ref "D124") (pin "11") (pinfunction "11_11") (pintype "passive"))
      (node (ref "D140") (pin "12") (pinfunction "12_12") (pintype "passive"))
    )
    (net (code "56") (name "Net-(D125-Pad11)") (class "Default")
      (node (ref "D125") (pin "11") (pinfunction "11_11") (pintype "passive"))
      (node (ref "D141") (pin "12") (pinfunction "12_12") (pintype "passive"))
    )
    (net (code "57") (name "Net-(D126-Pad11)") (class "Default")
      (node (ref "D126") (pin "11") (pinfunction "11_11") (pintype "passive"))
      (node (ref "D142") (pin "12") (pinfunction "12_12") (pintype "passive"))
    )
    (net (code "58") (name "Net-(D127-Pad11)") (class "Default")
      (node (ref "D127") (pin "11") (pinfunction "11_11") (pintype "passive"))
      (node (ref "D143") (pin "12") (pinfunction "12_12") (pintype "passive"))
    )
    (net (code "59") (name "Net-(D128-Pad11)") (class "Default")
      (node (ref "D128") (pin "11") (pinfunction "11_11") (pintype "passive"))
      (node (ref "D144") (pin "12") (pinfunction "12_12") (pintype "passive"))
    )
    (net (code "60") (name "Net-(D129-Pad11)") (class "Default")
      (node (ref "D129") (pin "11") (pinfunction "11_11") (pintype "passive"))
      (node (ref "D145") (pin "12") (pinfunction "12_12") (pintype "passive"))
    )
    (net (code "61") (name "Net-(D130-Pad11)") (class "Default")
      (node (ref "D130") (pin "11") (pinfunction "11_11") (pintype "passive"))
      (node (ref "D146") (pin "12") (pinfunction "12_12") (pintype "passive"))
    )
    (net (code "62") (name "Net-(D131-Pad11)") (class "Default")
      (node (ref "D131") (pin "11") (pinfunction "11_11") (pintype "passive"))
      (node (ref "D147") (pin "12") (pinfunction "12_12") (pintype "passive"))
    )
    (net (code "63") (name "Net-(D132-Pad11)") (class "Default")
      (node (ref "D132") (pin "11") (pinfunction "11_11") (pintype "passive"))
      (node (ref "D148") (pin "12") (pinfunction "12_12") (pintype "passive"))
    )
    (net (code "64") (name "Net-(D133-Pad11)") (class "Default")
      (node (ref "D133") (pin "11") (pinfunction "11_11") (pintype "passive"))
      (node (ref "D149") (pin "12") (pinfunction "12_12") (pintype "passive"))
    )
    (net (code "65") (name "Net-(D134-Pad11)") (class "Default")
      (node (ref "D134") (pin "11") (pinfunction "11_11") (pintype "passive"))
      (node (ref "D150") (pin "12") (pinfunction "12_12") (pintype "passive"))
    )
    (net (code "66") (name "Net-(D135-Pad11)") (class "Default")
      (node (ref "D135") (pin "11") (pinfunction "11_11") (pintype "passive"))
      (node (ref "D151") (pin "12") (pinfunction "12_12") (pintype "passive"))
    )
    (net (code "67") (name "Net-(D136-Pad11)") (class "Default")
      (node (ref "D136") (pin "11") (pinfunction "11_11") (pintype "passive"))
      (node (ref "D152") (pin "12") (pinfunction "12_12") (pintype "passive"))
    )
    (net (code "68") (name "Net-(D137-Pad11)") (class "Default")
      (node (ref "D137") (pin "11") (pinfunction "11_11") (pintype "passive"))
      (node (ref "D153") (pin "12") (pinfunction "12_12") (pintype "passive"))
    )
    (net (code "69") (name "Net-(D138-Pad11)") (class "Default")
      (node (ref "D138") (pin "11") (pinfunction "11_11") (pintype "passive"))
      (node (ref "D154") (pin "12") (pinfunction "12_12") (pintype "passive"))
    )
    (net (code "70") (name "Net-(D139-Pad11)") (class "Default")
      (node (ref "D139") (pin "11") (pinfunction "11_11") (pintype "passive"))
      (node (ref "D155") (pin "12") (pinfunction "12_12") (pintype "passive"))
    )
    (net (code "71") (name "Net-(D140-Pad11)") (class "Default")
      (node (ref "D140") (pin "11") (pinfunction "11_11") (pintype "passive"))
      (node (ref "D156") (pin "12") (pinfunction "12_12") (pintype "passive"))
    )
    (net (code "72") (name "Net-(D141-Pad11)") (class "Default")
      (node (ref "D141") (pin "11") (pinfunction "11_11") (pintype "passive"))
      (node (ref "D157") (pin "12") (pinfunction "12_12") (pintype "passive"))
    )
    (net (code "73") (name "Net-(D142-Pad11)") (class "Default")
      (node (ref "D142") (pin "11") (pinfunction "11_11") (pintype "passive"))
      (node (ref "D158") (pin "12") (pinfunction "12_12") (pintype "passive"))
    )
    (net (code "74") (name "Net-(D143-Pad11)") (class "Default")
      (node (ref "D143") (pin "11") (pinfunction "11_11") (pintype "passive"))
      (node (ref "D159") (pin "12") (pinfunction "12_12") (pintype "passive"))
    )
    (net (code "75") (name "Net-(D144-Pad11)") (class "Default")
      (node (ref "D144") (pin "11") (pinfunction "11_11") (pintype "passive"))
      (node (ref "D160") (pin "12") (pinfunction "12_12") (pintype "passive"))
    )
    (net (code "76") (name "Net-(D145-Pad11)") (class "Default")
      (node (ref "D145") (pin "11") (pinfunction "11_11") (pintype "passive"))
      (node (ref "D161") (pin "12") (pinfunction "12_12") (pintype "passive"))
    )
    (net (code "77") (name "Net-(D146-Pad11)") (class "Default")
      (node (ref "D146") (pin "11") (pinfunction "11_11") (pintype "passive"))
      (node (ref "D162") (pin "12") (pinfunction "12_12") (pintype "passive"))
    )
    (net (code "78") (name "Net-(D147-Pad11)") (class "Default")
      (node (ref "D147") (pin "11") (pinfunction "11_11") (pintype "passive"))
      (node (ref "R48") (pin "48") (pinfunction "48_48") (pintype "passive"))
    )
    (net (code "79") (name "Net-(D148-Pad11)") (class "Default")
      (node (ref "D148") (pin "11") (pinfunction "11_11") (pintype "passive"))
      (node (ref "R49") (pin "48") (pinfunction "48_48") (pintype "passive"))
    )
    (net (code "80") (name "Net-(D149-Pad11)") (class "Default")
      (node (ref "D149") (pin "11") (pinfunction "11_11") (pintype "passive"))
      (node (ref "R50") (pin "48") (pinfunction "48_48") (pintype "passive"))
    )
    (net (code "81") (name "Net-(D150-Pad11)") (class "Default")
      (node (ref "D150") (pin "11") (pinfunction "11_11") (pintype "passive"))
      (node (ref "R51") (pin "48") (pinfunction "48_48") (pintype "passive"))
    )
    (net (code "82") (name "Net-(D151-Pad11)") (class "Default")
      (node (ref "D151") (pin "11") (pinfunction "11_11") (pintype "passive"))
      (node (ref "R52") (pin "48") (pinfunction "48_48") (pintype "passive"))
    )
    (net (code "83") (name "Net-(D152-Pad11)") (class "Default")
      (node (ref "D152") (pin "11") (pinfunction "11_11") (pintype "passive"))
      (node (ref "R53") (pin "48") (pinfunction "48_48") (pintype "passive"))
    )
    (net (code "84") (name "Net-(D153-Pad11)") (class "Default")
      (node (ref "D153") (pin "11") (pinfunction "11_11") (pintype "passive"))
      (node (ref "R54") (pin "48") (pinfunction "48_48") (pintype "passive"))
    )
    (net (code "85") (name "Net-(D154-Pad11)") (class "Default")
      (node (ref "D154") (pin "11") (pinfunction "11_11") (pintype "passive"))
      (node (ref "R55") (pin "48") (pinfunction "48_48") (pintype "passive"))
    )
    (net (code "86") (name "Net-(D155-Pad11)") (class "Default")
      (node (ref "D155") (pin "11") (pinfunction "11_11") (pintype "passive"))
      (node (ref "R56") (pin "48") (pinfunction "48_48") (pintype "passive"))
    )
    (net (code "87") (name "Net-(D156-Pad11)") (class "Default")
      (node (ref "D156") (pin "11") (pinfunction "11_11") (pintype "passive"))
      (node (ref "R57") (pin "48") (pinfunction "48_48") (pintype "passive"))
    )
    (net (code "88") (name "Net-(D157-Pad11)") (class "Default")
      (node (ref "D157") (pin "11") (pinfunction "11_11") (pintype "passive"))
      (node (ref "R58") (pin "48") (pinfunction "48_48") (pintype "passive"))
    )
    (net (code "89") (name "Net-(D158-Pad11)") (class "Default")
      (node (ref "D158") (pin "11") (pinfunction "11_11") (pintype "passive"))
      (node (ref "R59") (pin "48") (pinfunction "48_48") (pintype "passive"))
    )
    (net (code "90") (name "Net-(D159-Pad11)") (class "Default")
      (node (ref "D159") (pin "11") (pinfunction "11_11") (pintype "passive"))
      (node (ref "R60") (pin "48") (pinfunction "48_48") (pintype "passive"))
    )
    (net (code "91") (name "Net-(D160-Pad11)") (class "Default")
      (node (ref "D160") (pin "11") (pinfunction "11_11") (pintype "passive"))
      (node (ref "R61") (pin "48") (pinfunction "48_48") (pintype "passive"))
    )
    (net (code "92") (name "Net-(D161-Pad11)") (class "Default")
      (node (ref "D161") (pin "11") (pinfunction "11_11") (pintype "passive"))
      (node (ref "R62") (pin "48") (pinfunction "48_48") (pintype "passive"))
    )
    (net (code "93") (name "Net-(D162-Pad11)") (class "Default")
      (node (ref "D162") (pin "11") (pinfunction "11_11") (pintype "passive"))
      (node (ref "R63") (pin "48") (pinfunction "48_48") (pintype "passive"))
    )
  )
)
